# Connector_Card1.net
KiCad netlist of a schematic drawn in Altium Designer
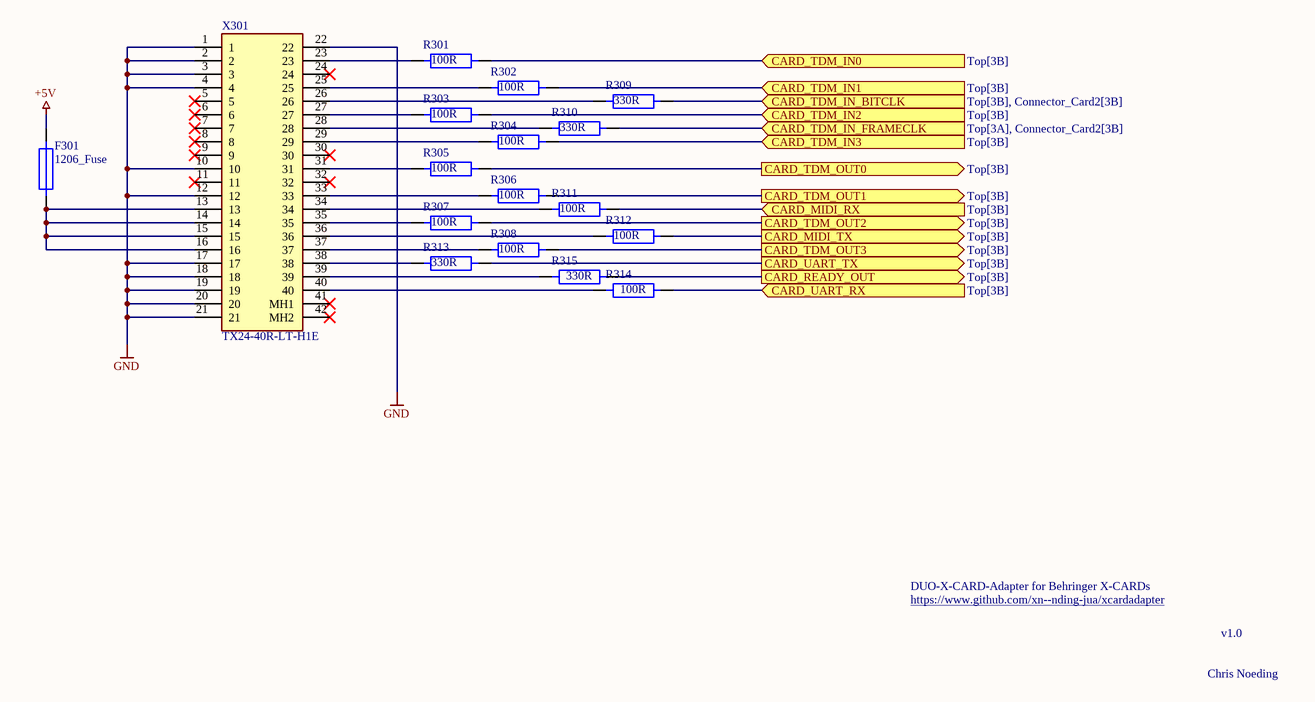
[diagram p0: Connector_Card1.SchDoc]

(export (version "E")
  (design (tool "Eeschema 10.0.6"))
  (components
    (comp (ref "F301")
      (value "1206_Fuse")
      (footprint "1206")
      (libsource (lib "FPGA_Board_Library") (part "1206_Fuse"))
    )
    (comp (ref "R301")
      (value "100R")
      (footprint "1206")
      (description "1206_R")
      (libsource (lib "FPGA_Board_Library") (part "1206_R"))
    )
    (comp (ref "R302")
      (value "100R")
      (footprint "1206")
      (description "1206_R")
      (libsource (lib "FPGA_Board_Library") (part "1206_R"))
    )
    (comp (ref "R303")
      (value "100R")
      (footprint "1206")
      (description "1206_R")
      (libsource (lib "FPGA_Board_Library") (part "1206_R"))
    )
    (comp (ref "R304")
      (value "100R")
      (footprint "1206")
      (description "1206_R")
      (libsource (lib "FPGA_Board_Library") (part "1206_R"))
    )
    (comp (ref "R305")
      (value "100R")
      (footprint "1206")
      (description "330R")
      (libsource (lib "FPGA_Board_Library") (part "1206_R"))
    )
    (comp (ref "R306")
      (value "100R")
      (footprint "1206")
      (description "330R")
      (libsource (lib "FPGA_Board_Library") (part "1206_R"))
    )
    (comp (ref "R307")
      (value "100R")
      (footprint "1206")
      (description "1206_R")
      (libsource (lib "FPGA_Board_Library") (part "1206_R"))
    )
    (comp (ref "R308")
      (value "100R")
      (footprint "1206")
      (description "1206_R")
      (libsource (lib "FPGA_Board_Library") (part "1206_R"))
    )
    (comp (ref "R309")
      (value "330R")
      (footprint "1206")
      (description "1206_R")
      (libsource (lib "FPGA_Board_Library") (part "1206_R"))
    )
    (comp (ref "R310")
      (value "330R")
      (footprint "1206")
      (description "1206_R")
      (libsource (lib "FPGA_Board_Library") (part "1206_R"))
    )
    (comp (ref "R311")
      (value "100R")
      (footprint "1206")
      (description "1206_R")
      (libsource (lib "FPGA_Board_Library") (part "1206_R"))
    )
    (comp (ref "R312")
      (value "100R")
      (footprint "1206")
      (description "1206_R")
      (libsource (lib "FPGA_Board_Library") (part "1206_R"))
    )
    (comp (ref "R313")
      (value "330R")
      (footprint "1206")
      (description "1206_R")
      (libsource (lib "FPGA_Board_Library") (part "1206_R"))
    )
    (comp (ref "R314")
      (value "100R")
      (footprint "1206")
      (description "1206_R")
      (libsource (lib "FPGA_Board_Library") (part "1206_R"))
    )
    (comp (ref "R315")
      (value "330R")
      (footprint "1206")
      (description "1206_R")
      (libsource (lib "FPGA_Board_Library") (part "1206_R"))
    )
    (comp (ref "X301")
      (value "TX24-40R-LT-H1E")
      (footprint "SamacSys:TX2440RLTH1E")
      (description "Connector")
      (fields (field (name "MOUSER PART NUMBER") "656-TX24-40R-LT-H1E"))
      (libsource (lib "*") (part "TX24-40R-LT-H1E"))
    )
  )
  (nets
    (net (code "1") (name "+5V") (class "Default")
      (node (ref "F301") (pin "2") (pinfunction "2_2") (pintype "passive"))
    )
    (net (code "2") (name "/CARD_MIDI_RX") (class "Default")
      (node (ref "R311") (pin "2") (pinfunction "2_2") (pintype "passive"))
    )
    (net (code "3") (name "/CARD_MIDI_TX") (class "Default")
      (node (ref "R312") (pin "2") (pinfunction "2_2") (pintype "passive"))
    )
    (net (code "4") (name "/CARD_READY_OUT") (class "Default")
      (node (ref "R315") (pin "2") (pinfunction "2_2") (pintype "passive"))
    )
    (net (code "5") (name "/CARD_TDM_IN0") (class "Default")
      (node (ref "R301") (pin "2") (pinfunction "2_2") (pintype "passive"))
    )
    (net (code "6") (name "/CARD_TDM_IN1") (class "Default")
      (node (ref "R302") (pin "2") (pinfunction "2_2") (pintype "passive"))
    )
    (net (code "7") (name "/CARD_TDM_IN2") (class "Default")
      (node (ref "R303") (pin "2") (pinfunction "2_2") (pintype "passive"))
    )
    (net (code "8") (name "/CARD_TDM_IN3") (class "Default")
      (node (ref "R304") (pin "2") (pinfunction "2_2") (pintype "passive"))
    )
    (net (code "9") (name "/CARD_TDM_IN_BITCLK") (class "Default")
      (node (ref "R309") (pin "2") (pinfunction "2_2") (pintype "passive"))
    )
    (net (code "10") (name "/CARD_TDM_IN_FRAMECLK") (class "Default")
      (node (ref "R310") (pin "2") (pinfunction "2_2") (pintype "passive"))
    )
    (net (code "11") (name "/CARD_TDM_OUT0") (class "Default")
      (node (ref "R305") (pin "2") (pinfunction "2_2") (pintype "passive"))
    )
    (net (code "12") (name "/CARD_TDM_OUT1") (class "Default")
      (node (ref "R306") (pin "2") (pinfunction "2_2") (pintype "passive"))
    )
    (net (code "13") (name "/CARD_TDM_OUT2") (class "Default")
      (node (ref "R307") (pin "2") (pinfunction "2_2") (pintype "passive"))
    )
    (net (code "14") (name "/CARD_TDM_OUT3") (class "Default")
      (node (ref "R308") (pin "2") (pinfunction "2_2") (pintype "passive"))
    )
    (net (code "15") (name "/CARD_UART_RX") (class "Default")
      (node (ref "R314") (pin "2") (pinfunction "2_2") (pintype "passive"))
    )
    (net (code "16") (name "/CARD_UART_TX") (class "Default")
      (node (ref "R313") (pin "2") (pinfunction "2_2") (pintype "passive"))
    )
    (net (code "17") (name "GND") (class "Default")
      (node (ref "X301") (pin "1") (pinfunction "1_1") (pintype "passive"))
      (node (ref "X301") (pin "10") (pinfunction "10_10") (pintype "passive"))
      (node (ref "X301") (pin "12") (pinfunction "12_12") (pintype "passive"))
      (node (ref "X301") (pin "17") (pinfunction "17_17") (pintype "passive"))
      (node (ref "X301") (pin "18") (pinfunction "18_18") (pintype "passive"))
      (node (ref "X301") (pin "19") (pinfunction "19_19") (pintype "passive"))
      (node (ref "X301") (pin "2") (pinfunction "2_2") (pintype "passive"))
      (node (ref "X301") (pin "20") (pinfunction "20_20") (pintype "passive"))
      (node (ref "X301") (pin "21") (pinfunction "21_21") (pintype "passive"))
      (node (ref "X301") (pin "22") (pinfunction "22_22") (pintype "passive"))
      (node (ref "X301") (pin "3") (pinfunction "3_3") (pintype "passive"))
      (node (ref "X301") (pin "4") (pinfunction "4_4") (pintype "passive"))
    )
    (net (code "18") (name "Net-(F301-Pad1)") (class "Default")
      (node (ref "F301") (pin "1") (pinfunction "1_1") (pintype "passive"))
      (node (ref "X301") (pin "13") (pinfunction "13_13") (pintype "passive"))
      (node (ref "X301") (pin "14") (pinfunction "14_14") (pintype "passive"))
      (node (ref "X301") (pin "15") (pinfunction "15_15") (pintype "passive"))
      (node (ref "X301") (pin "16") (pinfunction "16_16") (pintype "passive"))
    )
    (net (code "19") (name "Net-(R301-Pad1)") (class "Default")
      (node (ref "R301") (pin "1") (pinfunction "1_1") (pintype "passive"))
      (node (ref "X301") (pin "23") (pinfunction "23_23") (pintype "passive"))
    )
    (net (code "20") (name "Net-(R302-Pad1)") (class "Default")
      (node (ref "R302") (pin "1") (pinfunction "1_1") (pintype "passive"))
      (node (ref "X301") (pin "25") (pinfunction "25_25") (pintype "passive"))
    )
    (net (code "21") (name "Net-(R303-Pad1)") (class "Default")
      (node (ref "R303") (pin "1") (pinfunction "1_1") (pintype "passive"))
      (node (ref "X301") (pin "27") (pinfunction "27_27") (pintype "passive"))
    )
    (net (code "22") (name "Net-(R304-Pad1)") (class "Default")
      (node (ref "R304") (pin "1") (pinfunction "1_1") (pintype "passive"))
      (node (ref "X301") (pin "29") (pinfunction "29_29") (pintype "passive"))
    )
    (net (code "23") (name "Net-(R305-Pad1)") (class "Default")
      (node (ref "R305") (pin "1") (pinfunction "1_1") (pintype "passive"))
      (node (ref "X301") (pin "31") (pinfunction "31_31") (pintype "passive"))
    )
    (net (code "24") (name "Net-(R306-Pad1)") (class "Default")
      (node (ref "R306") (pin "1") (pinfunction "1_1") (pintype "passive"))
      (node (ref "X301") (pin "33") (pinfunction "33_33") (pintype "passive"))
    )
    (net (code "25") (name "Net-(R307-Pad1)") (class "Default")
      (node (ref "R307") (pin "1") (pinfunction "1_1") (pintype "passive"))
      (node (ref "X301") (pin "35") (pinfunction "35_35") (pintype "passive"))
    )
    (net (code "26") (name "Net-(R308-Pad1)") (class "Default")
      (node (ref "R308") (pin "1") (pinfunction "1_1") (pintype "passive"))
      (node (ref "X301") (pin "37") (pinfunction "37_37") (pintype "passive"))
    )
    (net (code "27") (name "Net-(R309-Pad1)") (class "Default")
      (node (ref "R309") (pin "1") (pinfunction "1_1") (pintype "passive"))
      (node (ref "X301") (pin "26") (pinfunction "26_26") (pintype "passive"))
    )
    (net (code "28") (name "Net-(R310-Pad1)") (class "Default")
      (node (ref "R310") (pin "1") (pinfunction "1_1") (pintype "passive"))
      (node (ref "X301") (pin "28") (pinfunction "28_28") (pintype "passive"))
    )
    (net (code "29") (name "Net-(R311-Pad1)") (class "Default")
      (node (ref "R311") (pin "1") (pinfunction "1_1") (pintype "passive"))
      (node (ref "X301") (pin "34") (pinfunction "34_34") (pintype "passive"))
    )
    (net (code "30") (name "Net-(R312-Pad1)") (class "Default")
      (node (ref "R312") (pin "1") (pinfunction "1_1") (pintype "passive"))
      (node (ref "X301") (pin "36") (pinfunction "36_36") (pintype "passive"))
    )
    (net (code "31") (name "Net-(R313-Pad1)") (class "Default")
      (node (ref "R313") (pin "1") (pinfunction "1_1") (pintype "passive"))
      (node (ref "X301") (pin "38") (pinfunction "38_38") (pintype "passive"))
    )
    (net (code "32") (name "Net-(R314-Pad1)") (class "Default")
      (node (ref "R314") (pin "1") (pinfunction "1_1") (pintype "passive"))
      (node (ref "X301") (pin "40") (pinfunction "40_40") (pintype "passive"))
    )
    (net (code "33") (name "Net-(R315-Pad1)") (class "Default")
      (node (ref "R315") (pin "1") (pinfunction "1_1") (pintype "passive"))
      (node (ref "X301") (pin "39") (pinfunction "39_39") (pintype "passive"))
    )
    (net (code "34") (name "unconnected-(X301-MH1-Pad41)") (class "Default")
      (node (ref "X301") (pin "41") (pinfunction "MH1_41") (pintype "passive+no_connect"))
    )
    (net (code "35") (name "unconnected-(X301-MH2-Pad42)") (class "Default")
      (node (ref "X301") (pin "42") (pinfunction "MH2_42") (pintype "passive+no_connect"))
    )
    (net (code "36") (name "unconnected-(X301-Pad5)") (class "Default")
      (node (ref "X301") (pin "5") (pinfunction "5_5") (pintype "passive+no_connect"))
    )
    (net (code "37") (name "unconnected-(X301-Pad6)") (class "Default")
      (node (ref "X301") (pin "6") (pinfunction "6_6") (pintype "passive+no_connect"))
    )
    (net (code "38") (name "unconnected-(X301-Pad7)") (class "Default")
      (node (ref "X301") (pin "7") (pinfunction "7_7") (pintype "passive+no_connect"))
    )
    (net (code "39") (name "unconnected-(X301-Pad8)") (class "Default")
      (node (ref "X301") (pin "8") (pinfunction "8_8") (pintype "passive+no_connect"))
    )
    (net (code "40") (name "unconnected-(X301-Pad9)") (class "Default")
      (node (ref "X301") (pin "9") (pinfunction "9_9") (pintype "passive+no_connect"))
    )
    (net (code "41") (name "unconnected-(X301-Pad11)") (class "Default")
      (node (ref "X301") (pin "11") (pinfunction "11_11") (pintype "passive+no_connect"))
    )
    (net (code "42") (name "unconnected-(X301-Pad24)") (class "Default")
      (node (ref "X301") (pin "24") (pinfunction "24_24") (pintype "passive+no_connect"))
    )
    (net (code "43") (name "unconnected-(X301-Pad30)") (class "Default")
      (node (ref "X301") (pin "30") (pinfunction "30_30") (pintype "passive+no_connect"))
    )
    (net (code "44") (name "unconnected-(X301-Pad32)") (class "Default")
      (node (ref "X301") (pin "32") (pinfunction "32_32") (pintype "passive+no_connect"))
    )
  )
)
